# Microcontroller.net
KiCad netlist of a schematic drawn in Altium Designer
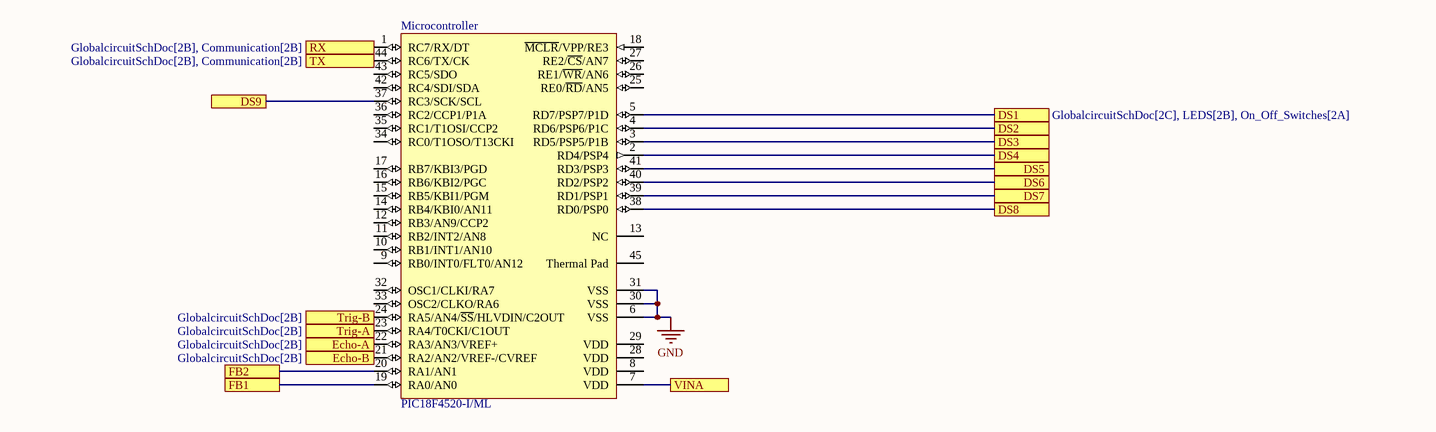
[diagram p0: Microcontroller.SchDoc]

(export (version "E")
  (design (tool "Eeschema 10.0.6"))
  (components
    (comp (ref "Microcontroller")
      (value "PIC18F4520-I/ML")
      (footprint "QFN-ML44_L")
      (libsource (lib "Altium Content Vault") (part "MC-8B-18F4520-SQ45"))
    )
  )
  (nets
    (net (code "1") (name "/DS1") (class "Default")
      (node (ref "Microcontroller") (pin "5") (pinfunction "RD7/PSP7/P1D_5") (pintype "bidirectional"))
    )
    (net (code "2") (name "/DS2") (class "Default")
      (node (ref "Microcontroller") (pin "4") (pinfunction "RD6/PSP6/P1C_4") (pintype "bidirectional"))
    )
    (net (code "3") (name "/DS3") (class "Default")
      (node (ref "Microcontroller") (pin "3") (pinfunction "RD5/PSP5/P1B_3") (pintype "bidirectional"))
    )
    (net (code "4") (name "/DS4") (class "Default")
      (node (ref "Microcontroller") (pin "2") (pinfunction "RD4/PSP4_2") (pintype "output"))
    )
    (net (code "5") (name "/DS5") (class "Default")
      (node (ref "Microcontroller") (pin "41") (pinfunction "RD3/PSP3_41") (pintype "bidirectional"))
    )
    (net (code "6") (name "/DS6") (class "Default")
      (node (ref "Microcontroller") (pin "40") (pinfunction "RD2/PSP2_40") (pintype "bidirectional"))
    )
    (net (code "7") (name "/DS7") (class "Default")
      (node (ref "Microcontroller") (pin "39") (pinfunction "RD1/PSP1_39") (pintype "bidirectional"))
    )
    (net (code "8") (name "/DS8") (class "Default")
      (node (ref "Microcontroller") (pin "38") (pinfunction "RD0/PSP0_38") (pintype "bidirectional"))
    )
    (net (code "9") (name "/DS9") (class "Default")
      (node (ref "Microcontroller") (pin "37") (pinfunction "RC3/SCK/SCL_37") (pintype "bidirectional"))
    )
    (net (code "10") (name "/Echo-A") (class "Default")
      (node (ref "Microcontroller") (pin "22") (pinfunction "RA3/AN3/VREF+_22") (pintype "bidirectional"))
    )
    (net (code "11") (name "/Echo-B") (class "Default")
      (node (ref "Microcontroller") (pin "21") (pinfunction "RA2/AN2/VREF-/CVREF_21") (pintype "bidirectional"))
    )
    (net (code "12") (name "/FB1") (class "Default")
      (node (ref "Microcontroller") (pin "19") (pinfunction "RA0/AN0_19") (pintype "bidirectional"))
    )
    (net (code "13") (name "/FB2") (class "Default")
      (node (ref "Microcontroller") (pin "20") (pinfunction "RA1/AN1_20") (pintype "bidirectional"))
    )
    (net (code "14") (name "/RX") (class "Default")
      (node (ref "Microcontroller") (pin "1") (pinfunction "RC7/RX/DT_1") (pintype "bidirectional"))
    )
    (net (code "15") (name "/TX") (class "Default")
      (node (ref "Microcontroller") (pin "44") (pinfunction "RC6/TX/CK_44") (pintype "bidirectional"))
    )
    (net (code "16") (name "/Trig-A") (class "Default")
      (node (ref "Microcontroller") (pin "23") (pinfunction "RA4/T0CKI/C1OUT_23") (pintype "bidirectional"))
    )
    (net (code "17") (name "/Trig-B") (class "Default")
      (node (ref "Microcontroller") (pin "24") (pinfunction "RA5/AN4/~{SS}/HLVDIN/C2OUT_24") (pintype "bidirectional"))
    )
    (net (code "18") (name "/VINA") (class "Default")
      (node (ref "Microcontroller") (pin "7") (pinfunction "VDD_7") (pintype "power_in"))
    )
    (net (code "19") (name "GND") (class "Default")
      (node (ref "Microcontroller") (pin "30") (pinfunction "VSS_30") (pintype "power_in"))
      (node (ref "Microcontroller") (pin "31") (pinfunction "VSS_31") (pintype "power_in"))
      (node (ref "Microcontroller") (pin "6") (pinfunction "VSS_6") (pintype "power_in"))
    )
    (net (code "20") (name "unconnected-(Microcontroller-NC-Pad13)") (class "Default")
      (node (ref "Microcontroller") (pin "13") (pinfunction "NC_13") (pintype "passive"))
    )
    (net (code "21") (name "unconnected-(Microcontroller-OSC1{slash}CLKI{slash}RA7-Pad32)") (class "Default")
      (node (ref "Microcontroller") (pin "32") (pinfunction "OSC1/CLKI/RA7_32") (pintype "bidirectional"))
    )
    (net (code "22") (name "unconnected-(Microcontroller-OSC2{slash}CLKO{slash}RA6-Pad33)") (class "Default")
      (node (ref "Microcontroller") (pin "33") (pinfunction "OSC2/CLKO/RA6_33") (pintype "bidirectional"))
    )
    (net (code "23") (name "unconnected-(Microcontroller-RB0{slash}INT0{slash}FLT0{slash}AN12-Pad9)") (class "Default")
      (node (ref "Microcontroller") (pin "9") (pinfunction "RB0/INT0/FLT0/AN12_9") (pintype "bidirectional"))
    )
    (net (code "24") (name "unconnected-(Microcontroller-RB1{slash}INT1{slash}AN10-Pad10)") (class "Default")
      (node (ref "Microcontroller") (pin "10") (pinfunction "RB1/INT1/AN10_10") (pintype "bidirectional"))
    )
    (net (code "25") (name "unconnected-(Microcontroller-RB2{slash}INT2{slash}AN8-Pad11)") (class "Default")
      (node (ref "Microcontroller") (pin "11") (pinfunction "RB2/INT2/AN8_11") (pintype "bidirectional"))
    )
    (net (code "26") (name "unconnected-(Microcontroller-RB3{slash}AN9{slash}CCP2-Pad12)") (class "Default")
      (node (ref "Microcontroller") (pin "12") (pinfunction "RB3/AN9/CCP2_12") (pintype "bidirectional"))
    )
    (net (code "27") (name "unconnected-(Microcontroller-RB4{slash}KBI0{slash}AN11-Pad14)") (class "Default")
      (node (ref "Microcontroller") (pin "14") (pinfunction "RB4/KBI0/AN11_14") (pintype "bidirectional"))
    )
    (net (code "28") (name "unconnected-(Microcontroller-RB5{slash}KBI1{slash}PGM-Pad15)") (class "Default")
      (node (ref "Microcontroller") (pin "15") (pinfunction "RB5/KBI1/PGM_15") (pintype "bidirectional"))
    )
    (net (code "29") (name "unconnected-(Microcontroller-RB6{slash}KBI2{slash}PGC-Pad16)") (class "Default")
      (node (ref "Microcontroller") (pin "16") (pinfunction "RB6/KBI2/PGC_16") (pintype "bidirectional"))
    )
    (net (code "30") (name "unconnected-(Microcontroller-RB7{slash}KBI3{slash}PGD-Pad17)") (class "Default")
      (node (ref "Microcontroller") (pin "17") (pinfunction "RB7/KBI3/PGD_17") (pintype "bidirectional"))
    )
    (net (code "31") (name "unconnected-(Microcontroller-RC0{slash}T1OSO{slash}T13CKI-Pad34)") (class "Default")
      (node (ref "Microcontroller") (pin "34") (pinfunction "RC0/T1OSO/T13CKI_34") (pintype "bidirectional"))
    )
    (net (code "32") (name "unconnected-(Microcontroller-RC1{slash}T1OSI{slash}CCP2-Pad35)") (class "Default")
      (node (ref "Microcontroller") (pin "35") (pinfunction "RC1/T1OSI/CCP2_35") (pintype "bidirectional"))
    )
    (net (code "33") (name "unconnected-(Microcontroller-RC2{slash}CCP1{slash}P1A-Pad36)") (class "Default")
      (node (ref "Microcontroller") (pin "36") (pinfunction "RC2/CCP1/P1A_36") (pintype "bidirectional"))
    )
    (net (code "34") (name "unconnected-(Microcontroller-RC4{slash}SDI{slash}SDA-Pad42)") (class "Default")
      (node (ref "Microcontroller") (pin "42") (pinfunction "RC4/SDI/SDA_42") (pintype "bidirectional"))
    )
    (net (code "35") (name "unconnected-(Microcontroller-RC5{slash}SDO-Pad43)") (class "Default")
      (node (ref "Microcontroller") (pin "43") (pinfunction "RC5/SDO_43") (pintype "bidirectional"))
    )
    (net (code "36") (name "unconnected-(Microcontroller-RE0{slash}~{RD}{slash}AN5-Pad25)") (class "Default")
      (node (ref "Microcontroller") (pin "25") (pinfunction "RE0/~{RD}/AN5_25") (pintype "bidirectional"))
    )
    (net (code "37") (name "unconnected-(Microcontroller-RE1{slash}~{WR}{slash}AN6-Pad26)") (class "Default")
      (node (ref "Microcontroller") (pin "26") (pinfunction "RE1/~{WR}/AN6_26") (pintype "bidirectional"))
    )
    (net (code "38") (name "unconnected-(Microcontroller-RE2{slash}~{CS}{slash}AN7-Pad27)") (class "Default")
      (node (ref "Microcontroller") (pin "27") (pinfunction "RE2/~{CS}/AN7_27") (pintype "bidirectional"))
    )
    (net (code "39") (name "unconnected-(Microcontroller-Thermal_Pad-Pad45)") (class "Default")
      (node (ref "Microcontroller") (pin "45") (pinfunction "Thermal_Pad_45") (pintype "power_in"))
    )
    (net (code "40") (name "unconnected-(Microcontroller-VDD-Pad8)") (class "Default")
      (node (ref "Microcontroller") (pin "8") (pinfunction "VDD_8") (pintype "power_in"))
    )
    (net (code "41") (name "unconnected-(Microcontroller-VDD-Pad28)") (class "Default")
      (node (ref "Microcontroller") (pin "28") (pinfunction "VDD_28") (pintype "power_in"))
    )
    (net (code "42") (name "unconnected-(Microcontroller-VDD-Pad29)") (class "Default")
      (node (ref "Microcontroller") (pin "29") (pinfunction "VDD_29") (pintype "power_in"))
    )
    (net (code "43") (name "unconnected-(Microcontroller-~{MCLR}{slash}VPP{slash}RE3-Pad18)") (class "Default")
      (node (ref "Microcontroller") (pin "18") (pinfunction "~{MCLR}/VPP/RE3_18") (pintype "input"))
    )
  )
)
